# schematic.net
KiCad netlist of a schematic drawn in Altium Designer
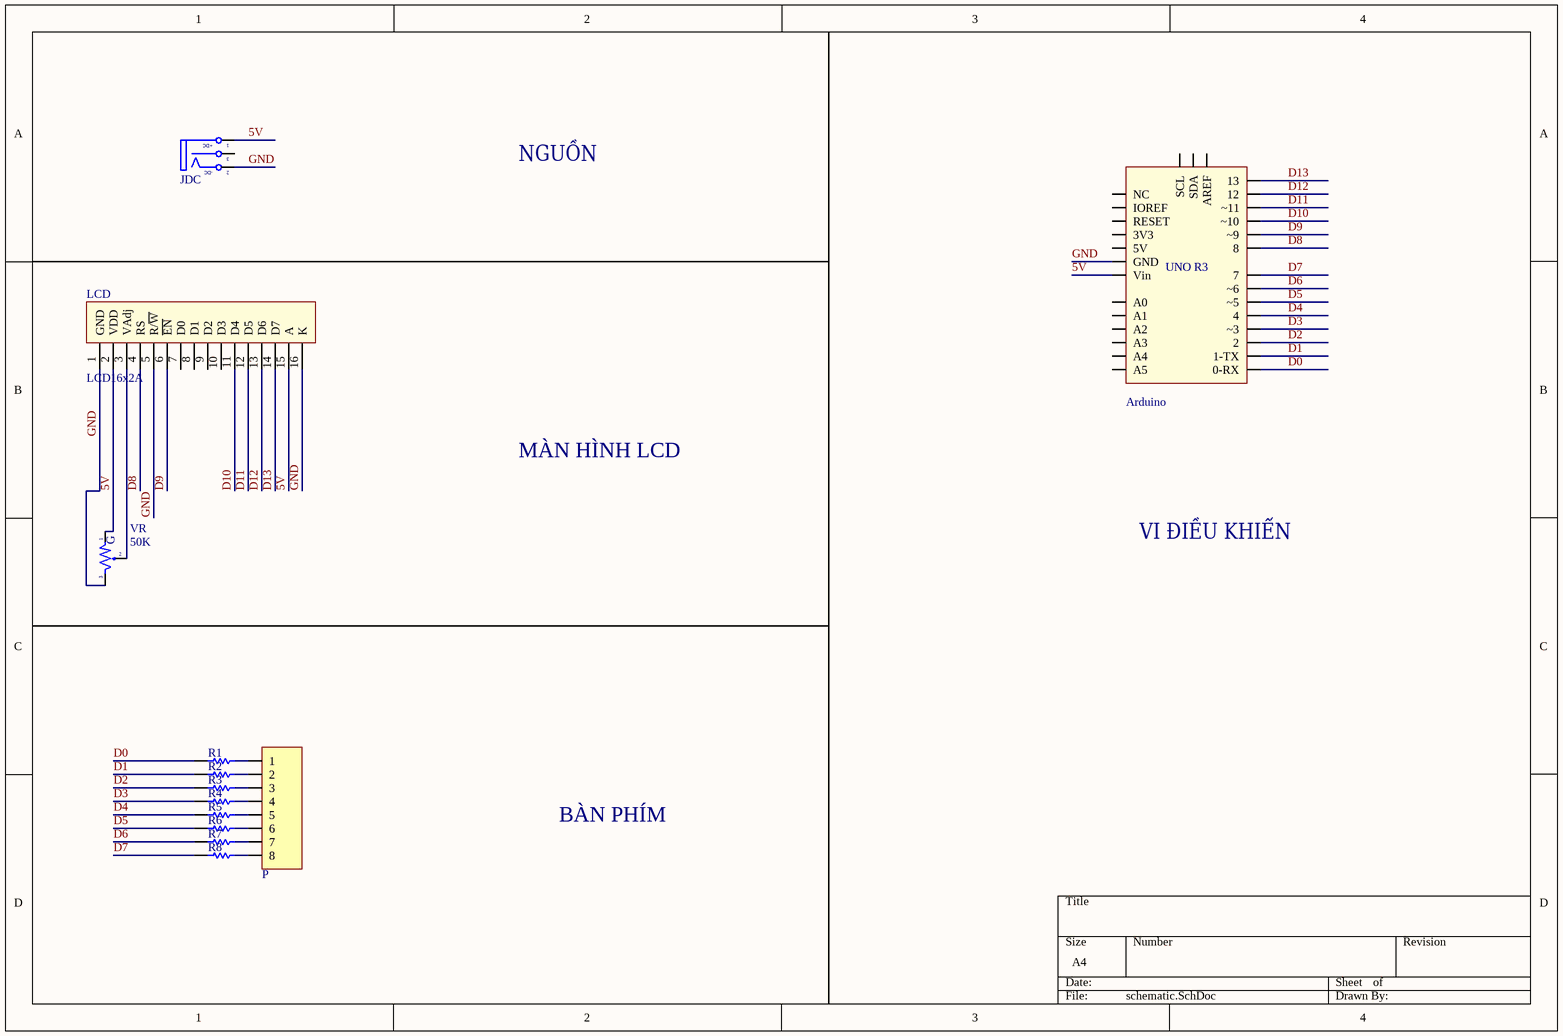
[diagram p0: schematic.SchDoc]

(export (version "E")
  (design (tool "Eeschema 10.0.6"))
  (components
    (comp (ref "Arduino")
      (value "Arduino Uno R3")
      (footprint "Arduino UNO R3")
      (description "Arduino UNO R3")
      (libsource (lib "TechMT.VN_Lib_Project v2") (part "Arduino Uno R3"))
    )
    (comp (ref "JDC")
      (value "Jack DC")
      (footprint "DC-IN")
      (description "Jack DC input")
      (libsource (lib "TechMT.VN_Lib_Project v1.0") (part "Jack DC"))
    )
    (comp (ref "LCD")
      (value "LCD16x2A")
      (footprint "LCD16X2")
      (description "LCD dipslay 16 char, 2 line")
      (libsource (lib "My library altium") (part "LCD16x2"))
    )
    (comp (ref "P")
      (value "Header 8")
      (footprint "JP8")
      (description "Header, 8-Pin")
      (fields (field (name "PUBLISHER") "Altium Limited"))
      (libsource (lib "TechMT.VN_Lib_Project v1.0") (part "Header 8"))
    )
    (comp (ref "R1")
      (value "R 0.5W")
      (footprint "R 0.5W")
      (libsource (lib "TechMT.VN_Lib_Project v1.0") (part "R 0.5W"))
    )
    (comp (ref "R2")
      (value "R 0.5W")
      (footprint "R 0.5W")
      (libsource (lib "TechMT.VN_Lib_Project v1.0") (part "R 0.5W"))
    )
    (comp (ref "R3")
      (value "R 0.5W")
      (footprint "R 0.5W")
      (libsource (lib "TechMT.VN_Lib_Project v1.0") (part "R 0.5W"))
    )
    (comp (ref "R4")
      (value "R 0.5W")
      (footprint "R 0.5W")
      (libsource (lib "TechMT.VN_Lib_Project v1.0") (part "R 0.5W"))
    )
    (comp (ref "R5")
      (value "R 0.5W")
      (footprint "R 0.5W")
      (libsource (lib "TechMT.VN_Lib_Project v1.0") (part "R 0.5W"))
    )
    (comp (ref "R6")
      (value "R 0.5W")
      (footprint "R 0.5W")
      (libsource (lib "TechMT.VN_Lib_Project v1.0") (part "R 0.5W"))
    )
    (comp (ref "R7")
      (value "R 0.5W")
      (footprint "R 0.5W")
      (libsource (lib "TechMT.VN_Lib_Project v1.0") (part "R 0.5W"))
    )
    (comp (ref "R8")
      (value "R 0.5W")
      (footprint "R 0.5W")
      (libsource (lib "TechMT.VN_Lib_Project v1.0") (part "R 0.5W"))
    )
    (comp (ref "VR")
      (value "50K")
      (footprint "VR-S1")
      (description "Var Resistor")
      (libsource (lib "TechMT.VN_Lib_Project v2") (part "VR-S"))
    )
  )
  (nets
    (net (code "1") (name "/5V") (class "Default")
      (node (ref "Arduino") (pin "Vin") (pinfunction "Vin_Vin") (pintype "passive"))
      (node (ref "JDC") (pin "1") (pinfunction "T_1") (pintype "passive"))
      (node (ref "LCD") (pin "15") (pinfunction "A_15") (pintype "passive"))
      (node (ref "LCD") (pin "2") (pinfunction "VDD_2") (pintype "passive"))
      (node (ref "VR") (pin "1") (pinfunction "1_1") (pintype "passive"))
    )
    (net (code "2") (name "/D0") (class "Default")
      (node (ref "Arduino") (pin "0-RX") (pinfunction "0-RX_0-RX") (pintype "passive"))
      (node (ref "R1") (pin "1") (pinfunction "1_1") (pintype "passive"))
    )
    (net (code "3") (name "/D1") (class "Default")
      (node (ref "Arduino") (pin "1-TX") (pinfunction "1-TX_1-TX") (pintype "passive"))
      (node (ref "R2") (pin "1") (pinfunction "1_1") (pintype "passive"))
    )
    (net (code "4") (name "/D2") (class "Default")
      (node (ref "Arduino") (pin "2") (pinfunction "2_2") (pintype "passive"))
      (node (ref "R3") (pin "1") (pinfunction "1_1") (pintype "passive"))
    )
    (net (code "5") (name "/D3") (class "Default")
      (node (ref "Arduino") (pin "~3") (pinfunction "~3_~3") (pintype "passive"))
      (node (ref "R4") (pin "1") (pinfunction "1_1") (pintype "passive"))
    )
    (net (code "6") (name "/D4") (class "Default")
      (node (ref "Arduino") (pin "4") (pinfunction "4_4") (pintype "passive"))
      (node (ref "R5") (pin "1") (pinfunction "1_1") (pintype "passive"))
    )
    (net (code "7") (name "/D5") (class "Default")
      (node (ref "Arduino") (pin "~5") (pinfunction "~5_~5") (pintype "passive"))
      (node (ref "R6") (pin "1") (pinfunction "1_1") (pintype "passive"))
    )
    (net (code "8") (name "/D6") (class "Default")
      (node (ref "Arduino") (pin "~6") (pinfunction "~6_~6") (pintype "passive"))
      (node (ref "R7") (pin "1") (pinfunction "1_1") (pintype "passive"))
    )
    (net (code "9") (name "/D7") (class "Default")
      (node (ref "Arduino") (pin "7") (pinfunction "7_7") (pintype "passive"))
      (node (ref "R8") (pin "1") (pinfunction "1_1") (pintype "passive"))
    )
    (net (code "10") (name "/D8") (class "Default")
      (node (ref "Arduino") (pin "8") (pinfunction "8_8") (pintype "passive"))
      (node (ref "LCD") (pin "4") (pinfunction "RS_4") (pintype "passive"))
    )
    (net (code "11") (name "/D9") (class "Default")
      (node (ref "Arduino") (pin "~9") (pinfunction "~9_~9") (pintype "passive"))
      (node (ref "LCD") (pin "6") (pinfunction "~{EN}_6") (pintype "passive"))
    )
    (net (code "12") (name "/D10") (class "Default")
      (node (ref "Arduino") (pin "~10") (pinfunction "~10_~10") (pintype "passive"))
      (node (ref "LCD") (pin "11") (pinfunction "D4_11") (pintype "passive"))
    )
    (net (code "13") (name "/D11") (class "Default")
      (node (ref "Arduino") (pin "~11") (pinfunction "~11_~11") (pintype "passive"))
      (node (ref "LCD") (pin "12") (pinfunction "D5_12") (pintype "passive"))
    )
    (net (code "14") (name "/D12") (class "Default")
      (node (ref "Arduino") (pin "12") (pinfunction "12_12") (pintype "passive"))
      (node (ref "LCD") (pin "13") (pinfunction "D6_13") (pintype "passive"))
    )
    (net (code "15") (name "/D13") (class "Default")
      (node (ref "Arduino") (pin "13") (pinfunction "13_13") (pintype "passive"))
      (node (ref "LCD") (pin "14") (pinfunction "D7_14") (pintype "passive"))
    )
    (net (code "16") (name "/GND") (class "Default")
      (node (ref "Arduino") (pin "GND") (pinfunction "GND_GND") (pintype "passive"))
      (node (ref "JDC") (pin "2") (pinfunction "TN_2") (pintype "passive"))
      (node (ref "LCD") (pin "1") (pinfunction "GND_1") (pintype "passive"))
      (node (ref "LCD") (pin "16") (pinfunction "K_16") (pintype "passive"))
      (node (ref "LCD") (pin "5") (pinfunction "R/~{W}_5") (pintype "passive"))
      (node (ref "VR") (pin "3") (pinfunction "3_3") (pintype "passive"))
    )
    (net (code "17") (name "Net-(LCD-VAdj)") (class "Default")
      (node (ref "LCD") (pin "3") (pinfunction "VAdj_3") (pintype "passive"))
      (node (ref "VR") (pin "2") (pinfunction "2_2") (pintype "passive"))
    )
    (net (code "18") (name "Net-(P-Pad1)") (class "Default")
      (node (ref "P") (pin "1") (pinfunction "1_1") (pintype "passive"))
      (node (ref "R1") (pin "2") (pinfunction "2_2") (pintype "passive"))
    )
    (net (code "19") (name "Net-(P-Pad2)") (class "Default")
      (node (ref "P") (pin "2") (pinfunction "2_2") (pintype "passive"))
      (node (ref "R2") (pin "2") (pinfunction "2_2") (pintype "passive"))
    )
    (net (code "20") (name "Net-(P-Pad3)") (class "Default")
      (node (ref "P") (pin "3") (pinfunction "3_3") (pintype "passive"))
      (node (ref "R3") (pin "2") (pinfunction "2_2") (pintype "passive"))
    )
    (net (code "21") (name "Net-(P-Pad4)") (class "Default")
      (node (ref "P") (pin "4") (pinfunction "4_4") (pintype "passive"))
      (node (ref "R4") (pin "2") (pinfunction "2_2") (pintype "passive"))
    )
    (net (code "22") (name "Net-(P-Pad5)") (class "Default")
      (node (ref "P") (pin "5") (pinfunction "5_5") (pintype "passive"))
      (node (ref "R5") (pin "2") (pinfunction "2_2") (pintype "passive"))
    )
    (net (code "23") (name "Net-(P-Pad6)") (class "Default")
      (node (ref "P") (pin "6") (pinfunction "6_6") (pintype "passive"))
      (node (ref "R6") (pin "2") (pinfunction "2_2") (pintype "passive"))
    )
    (net (code "24") (name "Net-(P-Pad7)") (class "Default")
      (node (ref "P") (pin "7") (pinfunction "7_7") (pintype "passive"))
      (node (ref "R7") (pin "2") (pinfunction "2_2") (pintype "passive"))
    )
    (net (code "25") (name "Net-(P-Pad8)") (class "Default")
      (node (ref "P") (pin "8") (pinfunction "8_8") (pintype "passive"))
      (node (ref "R8") (pin "2") (pinfunction "2_2") (pintype "passive"))
    )
    (net (code "26") (name "unconnected-(Arduino-Pad3V3)") (class "Default")
      (node (ref "Arduino") (pin "3V3") (pinfunction "3V3_3V3") (pintype "passive"))
    )
    (net (code "27") (name "unconnected-(Arduino-Pad5V)") (class "Default")
      (node (ref "Arduino") (pin "5V") (pinfunction "5V_5V") (pintype "passive"))
    )
    (net (code "28") (name "unconnected-(Arduino-PadA0)") (class "Default")
      (node (ref "Arduino") (pin "A0") (pinfunction "A0_A0") (pintype "passive"))
    )
    (net (code "29") (name "unconnected-(Arduino-PadA1)") (class "Default")
      (node (ref "Arduino") (pin "A1") (pinfunction "A1_A1") (pintype "passive"))
    )
    (net (code "30") (name "unconnected-(Arduino-PadA2)") (class "Default")
      (node (ref "Arduino") (pin "A2") (pinfunction "A2_A2") (pintype "passive"))
    )
    (net (code "31") (name "unconnected-(Arduino-PadA3)") (class "Default")
      (node (ref "Arduino") (pin "A3") (pinfunction "A3_A3") (pintype "passive"))
    )
    (net (code "32") (name "unconnected-(Arduino-PadA4)") (class "Default")
      (node (ref "Arduino") (pin "A4") (pinfunction "A4_A4") (pintype "passive"))
    )
    (net (code "33") (name "unconnected-(Arduino-PadA5)") (class "Default")
      (node (ref "Arduino") (pin "A5") (pinfunction "A5_A5") (pintype "passive"))
    )
    (net (code "34") (name "unconnected-(Arduino-PadAREF)") (class "Default")
      (node (ref "Arduino") (pin "AREF") (pinfunction "AREF_AREF") (pintype "passive"))
    )
    (net (code "35") (name "unconnected-(Arduino-PadIOREF)") (class "Default")
      (node (ref "Arduino") (pin "IOREF") (pinfunction "IOREF_IOREF") (pintype "passive"))
    )
    (net (code "36") (name "unconnected-(Arduino-PadNC)") (class "Default")
      (node (ref "Arduino") (pin "NC") (pinfunction "NC_NC") (pintype "passive"))
    )
    (net (code "37") (name "unconnected-(Arduino-PadRESET)") (class "Default")
      (node (ref "Arduino") (pin "RESET") (pinfunction "RESET_RESET") (pintype "passive"))
    )
    (net (code "38") (name "unconnected-(Arduino-PadSCL)") (class "Default")
      (node (ref "Arduino") (pin "SCL") (pinfunction "SCL_SCL") (pintype "passive"))
    )
    (net (code "39") (name "unconnected-(Arduino-PadSDA)") (class "Default")
      (node (ref "Arduino") (pin "SDA") (pinfunction "SDA_SDA") (pintype "passive"))
    )
    (net (code "40") (name "unconnected-(JDC-S-Pad3)") (class "Default")
      (node (ref "JDC") (pin "3") (pinfunction "S_3") (pintype "power_in"))
    )
    (net (code "41") (name "unconnected-(LCD-D0-Pad7)") (class "Default")
      (node (ref "LCD") (pin "7") (pinfunction "D0_7") (pintype "passive"))
    )
    (net (code "42") (name "unconnected-(LCD-D1-Pad8)") (class "Default")
      (node (ref "LCD") (pin "8") (pinfunction "D1_8") (pintype "passive"))
    )
    (net (code "43") (name "unconnected-(LCD-D2-Pad9)") (class "Default")
      (node (ref "LCD") (pin "9") (pinfunction "D2_9") (pintype "passive"))
    )
    (net (code "44") (name "unconnected-(LCD-D3-Pad10)") (class "Default")
      (node (ref "LCD") (pin "10") (pinfunction "D3_10") (pintype "passive"))
    )
  )
)
